# LCmeter0-LCD-8pinlcd-PIC18F2550-COMP.net
KiCad netlist of a schematic drawn in EAGLE
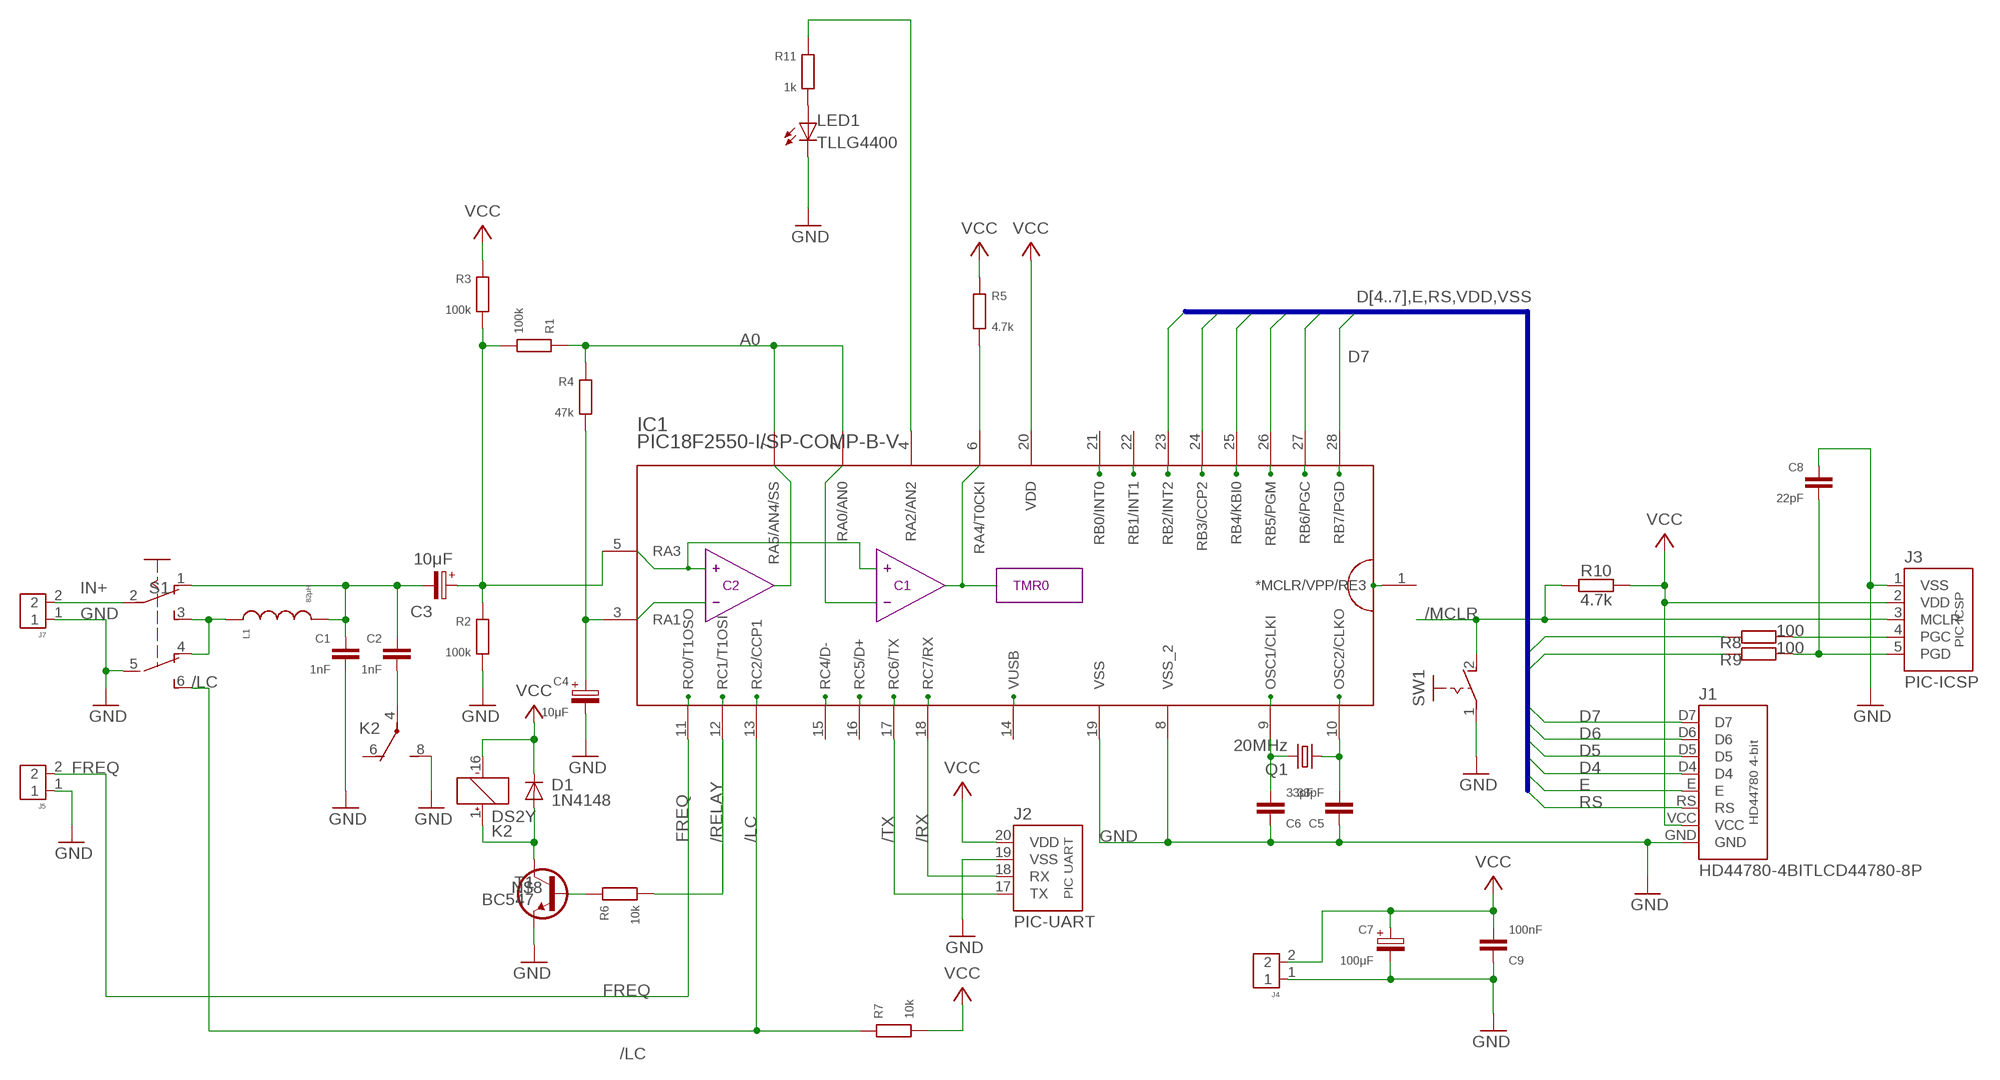
[diagram p0: schematic, sheet 1]

(export (version "E")
  (design (tool "Eeschema 10.0.6"))
  (components
    (comp (ref "C1")
      (value "1nF")
      (footprint "eagle-import:C050-025X060")
      (libsource (lib "eagle-import") (part "C025-025X060"))
    )
    (comp (ref "C2")
      (value "1nF")
      (footprint "eagle-import:C050-025X060")
      (libsource (lib "eagle-import") (part "C025-025X060"))
    )
    (comp (ref "C3")
      (value "10μF")
      (footprint "eagle-import:E2,5-4")
      (libsource (lib "eagle-import") (part "CPOLE2,5-4"))
    )
    (comp (ref "C4")
      (value "10μF")
      (footprint "eagle-import:E2,5-4")
      (libsource (lib "eagle-import") (part "CPOLE2,5-4"))
    )
    (comp (ref "C5")
      (value "33pF")
      (footprint "eagle-import:C025-020X036")
      (libsource (lib "eagle-import") (part "C025-020X036"))
    )
    (comp (ref "C6")
      (value "33pF")
      (footprint "eagle-import:C025-020X036")
      (libsource (lib "eagle-import") (part "C025-020X036"))
    )
    (comp (ref "C7")
      (value "100μF")
      (footprint "eagle-import:E2,5-5")
      (libsource (lib "eagle-import") (part "CPOLE2.5-5"))
    )
    (comp (ref "C8")
      (value "22pF")
      (footprint "eagle-import:C050-020X036")
      (libsource (lib "eagle-import") (part "C050-020X036"))
    )
    (comp (ref "C9")
      (value "100nF")
      (footprint "eagle-import:C025-020X036_V")
      (libsource (lib "eagle-import") (part "C025-020X036/V"))
    )
    (comp (ref "D1")
      (value "1N4148")
      (footprint "eagle-import:DO34-7")
      (libsource (lib "eagle-import") (part "1N414834-7"))
    )
    (comp (ref "IC1")
      (value "PIC18F2550-I/SP-COMP-B-V")
      (footprint "eagle-import:DIL28-3_V")
      (libsource (lib "eagle-import") (part "PIC18F2550-I/SP-COMP-B-V"))
    )
    (comp (ref "J1")
      (value "HD44780-4BITLCD44780-8P")
      (footprint "eagle-import:CONN-LCD44780")
      (libsource (lib "eagle-import") (part "HD44780-4BITLCD44780-8P"))
    )
    (comp (ref "J2")
      (value "PIC-UART")
      (footprint "eagle-import:PIC-UART")
      (libsource (lib "eagle-import") (part "PIC-UART"))
    )
    (comp (ref "J3")
      (value "PIC-ICSP")
      (footprint "eagle-import:PIC-ICSP")
      (libsource (lib "eagle-import") (part "PIC-ICSPICSP"))
    )
    (comp (ref "J4")
      (value "J4")
      (footprint "eagle-import:CONN-2P")
      (libsource (lib "eagle-import") (part "CONN-2P2P/H"))
    )
    (comp (ref "J5")
      (value "CONN-2P2P/V")
      (footprint "eagle-import:CONN-2P-V")
      (libsource (lib "eagle-import") (part "CONN-2P2P/V"))
    )
    (comp (ref "J7")
      (value "CONN-2P2P/V")
      (footprint "eagle-import:CONN-2P-V")
      (libsource (lib "eagle-import") (part "CONN-2P2P/V"))
    )
    (comp (ref "K2")
      (value "DS2Y")
      (footprint "eagle-import:DS2Y")
      (fields (field (name "MPN") "DS2Y-S-DC5V"))
      (libsource (lib "eagle-import") (part "DS2Y-S-DC5V"))
    )
    (comp (ref "L1")
      (value "82μH")
      (footprint "eagle-import:0207_10")
      (libsource (lib "eagle-import") (part "LAXIAL"))
    )
    (comp (ref "LED1")
      (value "TLLG4400")
      (footprint "eagle-import:LED3MM")
      (fields (field (name "MF") "VISHAY SEMICONDUCTOR"))
      (libsource (lib "eagle-import") (part "TLLG4400"))
    )
    (comp (ref "Q1")
      (value "20MHz")
      (footprint "eagle-import:HC49")
      (libsource (lib "eagle-import") (part "CRYSTALHC49"))
    )
    (comp (ref "R1")
      (value "100k")
      (footprint "eagle-import:0202_7")
      (libsource (lib "eagle-import") (part "R0202/7"))
    )
    (comp (ref "R2")
      (value "100k")
      (footprint "eagle-import:0202_7")
      (libsource (lib "eagle-import") (part "R0202/7"))
    )
    (comp (ref "R3")
      (value "100k")
      (footprint "eagle-import:0202_7")
      (libsource (lib "eagle-import") (part "R0202/7"))
    )
    (comp (ref "R4")
      (value "47k")
      (footprint "eagle-import:0202_7")
      (libsource (lib "eagle-import") (part "R0202/7"))
    )
    (comp (ref "R5")
      (value "4.7k")
      (footprint "eagle-import:0202_7")
      (libsource (lib "eagle-import") (part "R0202/7"))
    )
    (comp (ref "R6")
      (value "10k")
      (footprint "eagle-import:0202_7-V")
      (libsource (lib "eagle-import") (part "R0202/7-V"))
    )
    (comp (ref "R7")
      (value "10k")
      (footprint "eagle-import:0202_10-V")
      (libsource (lib "eagle-import") (part "R0202/10-V"))
    )
    (comp (ref "R8")
      (value "100")
      (footprint "eagle-import:0202_7-V")
      (libsource (lib "eagle-import") (part "R0202/7-V"))
    )
    (comp (ref "R9")
      (value "100")
      (footprint "eagle-import:0202_5-V")
      (libsource (lib "eagle-import") (part "R0202/5-V"))
    )
    (comp (ref "R10")
      (value "4.7k")
      (footprint "eagle-import:0202_7")
      (libsource (lib "eagle-import") (part "R0202/7"))
    )
    (comp (ref "R11")
      (value "1k")
      (footprint "eagle-import:0202_5-V")
      (libsource (lib "eagle-import") (part "R0202/5-V"))
    )
    (comp (ref "S1")
      (value "SL-SW-2P-2T")
      (footprint "eagle-import:SLSW-2P2T")
      (libsource (lib "eagle-import") (part "SL-SW-2P-2T"))
    )
    (comp (ref "SW1")
      (value "PB-1P-1T")
      (footprint "eagle-import:PB-1P1T")
      (libsource (lib "eagle-import") (part "PB-1P-1T"))
    )
    (comp (ref "T1")
      (value "BC547")
      (footprint "eagle-import:TO92-CBE-A")
      (libsource (lib "eagle-import") (part "BC547CBE-A"))
    )
  )
  (nets
    (net (code "3") (name "/A0") (class "Default")
      (node (ref "IC1") (pin "2") (pinfunction "RA0/AN0_2") (pintype "passive"))
      (node (ref "IC1") (pin "7") (pinfunction "RA5/AN4/SS_7") (pintype "passive"))
      (node (ref "R1") (pin "2") (pinfunction "2_2") (pintype "passive"))
      (node (ref "R4") (pin "2") (pinfunction "2_2") (pintype "passive"))
    )
    (net (code "4") (name "/D4") (class "Default")
      (node (ref "IC1") (pin "25") (pinfunction "RB4/KBI0_25") (pintype "passive"))
      (node (ref "J1") (pin "D4") (pinfunction "D4_D4") (pintype "passive"))
    )
    (net (code "5") (name "/D5") (class "Default")
      (node (ref "IC1") (pin "26") (pinfunction "RB5/PGM_26") (pintype "passive"))
      (node (ref "J1") (pin "D5") (pinfunction "D5_D5") (pintype "passive"))
    )
    (net (code "6") (name "/D6") (class "Default")
      (node (ref "IC1") (pin "27") (pinfunction "RB6/PGC_27") (pintype "passive"))
      (node (ref "J1") (pin "D6") (pinfunction "D6_D6") (pintype "passive"))
      (node (ref "R8") (pin "2") (pinfunction "2_2") (pintype "passive"))
    )
    (net (code "7") (name "/D7") (class "Default")
      (node (ref "IC1") (pin "28") (pinfunction "RB7/PGD_28") (pintype "passive"))
      (node (ref "J1") (pin "D7") (pinfunction "D7_D7") (pintype "passive"))
      (node (ref "R9") (pin "2") (pinfunction "2_2") (pintype "passive"))
    )
    (net (code "8") (name "/E") (class "Default")
      (node (ref "IC1") (pin "24") (pinfunction "RB3/CCP2_24") (pintype "passive"))
      (node (ref "J1") (pin "E") (pinfunction "E_E") (pintype "passive"))
    )
    (net (code "9") (name "/FREQ") (class "Default")
      (node (ref "IC1") (pin "11") (pinfunction "RC0/T1OSO_11") (pintype "passive"))
      (node (ref "J5") (pin "2") (pinfunction "2_2") (pintype "bidirectional"))
    )
    (net (code "10") (name "/IN+") (class "Default")
      (node (ref "J7") (pin "2") (pinfunction "2_2") (pintype "bidirectional"))
      (node (ref "S1") (pin "2") (pinfunction "P_2") (pintype "passive"))
    )
    (net (code "11") (name "/N$8") (class "Default")
      (node (ref "D1") (pin "A") (pinfunction "A_A") (pintype "passive"))
      (node (ref "K2") (pin "1") (pinfunction "+_1") (pintype "passive"))
      (node (ref "T1") (pin "C") (pinfunction "C_C") (pintype "passive"))
    )
    (net (code "12") (name "/RS") (class "Default")
      (node (ref "IC1") (pin "23") (pinfunction "RB2/INT2_23") (pintype "passive"))
      (node (ref "J1") (pin "RS") (pinfunction "RS_RS") (pintype "passive"))
    )
    (net (code "14") (name "/{slash}LC") (class "Default")
      (node (ref "IC1") (pin "13") (pinfunction "RC2/CCP1_13") (pintype "passive"))
      (node (ref "R7") (pin "2") (pinfunction "2_2") (pintype "passive"))
      (node (ref "S1") (pin "6") (pinfunction "S1_6") (pintype "passive"))
    )
    (net (code "15") (name "/{slash}MCLR") (class "Default")
      (node (ref "J3") (pin "3") (pinfunction "MCLR_3") (pintype "passive"))
      (node (ref "R10") (pin "2") (pinfunction "2_2") (pintype "passive"))
      (node (ref "SW1") (pin "2") (pinfunction "S_2") (pintype "passive"))
    )
    (net (code "16") (name "/{slash}RELAY") (class "Default")
      (node (ref "IC1") (pin "12") (pinfunction "RC1/T1OSI_12") (pintype "passive"))
      (node (ref "R6") (pin "1") (pinfunction "1_1") (pintype "passive"))
    )
    (net (code "17") (name "/{slash}RX") (class "Default")
      (node (ref "IC1") (pin "18") (pinfunction "RC7/RX_18") (pintype "passive"))
      (node (ref "J2") (pin "18") (pinfunction "RX_18") (pintype "passive"))
    )
    (net (code "18") (name "/{slash}TX") (class "Default")
      (node (ref "IC1") (pin "17") (pinfunction "RC6/TX_17") (pintype "passive"))
      (node (ref "J2") (pin "17") (pinfunction "TX_17") (pintype "passive"))
    )
    (net (code "19") (name "GND") (class "Default")
      (node (ref "C1") (pin "2") (pinfunction "2_2") (pintype "passive"))
      (node (ref "C4") (pin "-") (pinfunction "-_-") (pintype "passive"))
      (node (ref "C5") (pin "1") (pinfunction "1_1") (pintype "passive"))
      (node (ref "C6") (pin "1") (pinfunction "1_1") (pintype "passive"))
      (node (ref "C7") (pin "-") (pinfunction "-_-") (pintype "passive"))
      (node (ref "C8") (pin "1") (pinfunction "1_1") (pintype "passive"))
      (node (ref "C9") (pin "1") (pinfunction "1_1") (pintype "passive"))
      (node (ref "IC1") (pin "19") (pinfunction "VSS_19") (pintype "passive"))
      (node (ref "IC1") (pin "8") (pinfunction "VSS_2_8") (pintype "passive"))
      (node (ref "J1") (pin "GND") (pinfunction "GND_GND") (pintype "passive"))
      (node (ref "J2") (pin "19") (pinfunction "VSS_19") (pintype "passive"))
      (node (ref "J3") (pin "1") (pinfunction "VSS_1") (pintype "passive"))
      (node (ref "J4") (pin "1") (pinfunction "1_1") (pintype "bidirectional"))
      (node (ref "J5") (pin "1") (pinfunction "1_1") (pintype "bidirectional"))
      (node (ref "J7") (pin "1") (pinfunction "1_1") (pintype "bidirectional"))
      (node (ref "K2") (pin "8") (pinfunction "S_8") (pintype "passive"))
      (node (ref "LED1") (pin "K") (pinfunction "C_K") (pintype "passive"))
      (node (ref "R2") (pin "1") (pinfunction "1_1") (pintype "passive"))
      (node (ref "S1") (pin "5") (pinfunction "P1_5") (pintype "passive"))
      (node (ref "SW1") (pin "1") (pinfunction "P_1") (pintype "passive"))
      (node (ref "T1") (pin "E") (pinfunction "E_E") (pintype "passive"))
    )
    (net (code "20") (name "Net-(IC1-OSC1{slash}CLKI)") (class "Default")
      (node (ref "C6") (pin "2") (pinfunction "2_2") (pintype "passive"))
      (node (ref "IC1") (pin "9") (pinfunction "OSC1/CLKI_9") (pintype "passive"))
      (node (ref "Q1") (pin "2") (pinfunction "2_2") (pintype "passive"))
    )
    (net (code "21") (name "Net-(IC1-OSC2{slash}CLKO)") (class "Default")
      (node (ref "C5") (pin "2") (pinfunction "2_2") (pintype "passive"))
      (node (ref "IC1") (pin "10") (pinfunction "OSC2/CLKO_10") (pintype "passive"))
      (node (ref "Q1") (pin "1") (pinfunction "1_1") (pintype "passive"))
    )
    (net (code "22") (name "Net-(IC1-RA1)") (class "Default")
      (node (ref "C4") (pin "+") (pinfunction "+_+") (pintype "passive"))
      (node (ref "IC1") (pin "3") (pinfunction "RA1_3") (pintype "passive"))
      (node (ref "R4") (pin "1") (pinfunction "1_1") (pintype "passive"))
    )
    (net (code "23") (name "Net-(IC1-RA2{slash}AN2)") (class "Default")
      (node (ref "IC1") (pin "4") (pinfunction "RA2/AN2_4") (pintype "passive"))
      (node (ref "R11") (pin "2") (pinfunction "2_2") (pintype "passive"))
    )
    (net (code "24") (name "Net-(IC1-RA3)") (class "Default")
      (node (ref "C3") (pin "+") (pinfunction "+_+") (pintype "passive"))
      (node (ref "IC1") (pin "5") (pinfunction "RA3_5") (pintype "passive"))
      (node (ref "R1") (pin "1") (pinfunction "1_1") (pintype "passive"))
      (node (ref "R2") (pin "2") (pinfunction "2_2") (pintype "passive"))
      (node (ref "R3") (pin "1") (pinfunction "1_1") (pintype "passive"))
    )
    (net (code "25") (name "Net-(IC1-RA4{slash}T0CKI)") (class "Default")
      (node (ref "IC1") (pin "6") (pinfunction "RA4/T0CKI_6") (pintype "passive"))
      (node (ref "R5") (pin "1") (pinfunction "1_1") (pintype "passive"))
    )
    (net (code "26") (name "Net-(J3-PGC)") (class "Default")
      (node (ref "J3") (pin "4") (pinfunction "PGC_4") (pintype "passive"))
      (node (ref "R8") (pin "1") (pinfunction "1_1") (pintype "passive"))
    )
    (net (code "27") (name "Net-(J3-PGD)") (class "Default")
      (node (ref "C8") (pin "2") (pinfunction "2_2") (pintype "passive"))
      (node (ref "J3") (pin "5") (pinfunction "PGD_5") (pintype "passive"))
      (node (ref "R9") (pin "1") (pinfunction "1_1") (pintype "passive"))
    )
    (net (code "28") (name "Net-(K2B-P)") (class "Default")
      (node (ref "C2") (pin "2") (pinfunction "2_2") (pintype "passive"))
      (node (ref "K2") (pin "4") (pinfunction "P_4") (pintype "passive"))
    )
    (net (code "29") (name "Net-(LED1-PadA)") (class "Default")
      (node (ref "LED1") (pin "A") (pinfunction "A_A") (pintype "passive"))
      (node (ref "R11") (pin "1") (pinfunction "1_1") (pintype "passive"))
    )
    (net (code "30") (name "Net-(R6-Pad2)") (class "Default")
      (node (ref "R6") (pin "2") (pinfunction "2_2") (pintype "passive"))
      (node (ref "T1") (pin "B") (pinfunction "B_B") (pintype "passive"))
    )
    (net (code "31") (name "Net-(S1-O)") (class "Default")
      (node (ref "C1") (pin "1") (pinfunction "1_1") (pintype "passive"))
      (node (ref "C2") (pin "1") (pinfunction "1_1") (pintype "passive"))
      (node (ref "C3") (pin "-") (pinfunction "-_-") (pintype "passive"))
      (node (ref "L1") (pin "2") (pinfunction "2_2") (pintype "passive"))
      (node (ref "S1") (pin "1") (pinfunction "O_1") (pintype "passive"))
    )
    (net (code "32") (name "Net-(S1-O1)") (class "Default")
      (node (ref "L1") (pin "1") (pinfunction "1_1") (pintype "passive"))
      (node (ref "S1") (pin "3") (pinfunction "S_3") (pintype "passive"))
      (node (ref "S1") (pin "4") (pinfunction "O1_4") (pintype "passive"))
    )
    (net (code "33") (name "VCC") (class "Default")
      (node (ref "C7") (pin "+") (pinfunction "+_+") (pintype "passive"))
      (node (ref "C9") (pin "2") (pinfunction "2_2") (pintype "passive"))
      (node (ref "D1") (pin "C") (pinfunction "C_C") (pintype "passive"))
      (node (ref "IC1") (pin "20") (pinfunction "VDD_20") (pintype "passive"))
      (node (ref "J1") (pin "VCC") (pinfunction "VCC_VCC") (pintype "passive"))
      (node (ref "J2") (pin "20") (pinfunction "VDD_20") (pintype "passive"))
      (node (ref "J3") (pin "2") (pinfunction "VDD_2") (pintype "passive"))
      (node (ref "J4") (pin "2") (pinfunction "2_2") (pintype "bidirectional"))
      (node (ref "K2") (pin "16") (pinfunction "-_16") (pintype "passive"))
      (node (ref "R10") (pin "1") (pinfunction "1_1") (pintype "passive"))
      (node (ref "R3") (pin "2") (pinfunction "2_2") (pintype "passive"))
      (node (ref "R5") (pin "2") (pinfunction "2_2") (pintype "passive"))
      (node (ref "R7") (pin "1") (pinfunction "1_1") (pintype "passive"))
    )
    (net (code "34") (name "unconnected-(IC1-*MCLR{slash}VPP{slash}RE3-Pad1)") (class "Default")
      (node (ref "IC1") (pin "1") (pinfunction "*MCLR/VPP/RE3_1") (pintype "passive"))
    )
    (net (code "35") (name "unconnected-(IC1-RB0{slash}INT0-Pad21)") (class "Default")
      (node (ref "IC1") (pin "21") (pinfunction "RB0/INT0_21") (pintype "passive"))
    )
    (net (code "36") (name "unconnected-(IC1-RB1{slash}INT1-Pad22)") (class "Default")
      (node (ref "IC1") (pin "22") (pinfunction "RB1/INT1_22") (pintype "passive"))
    )
    (net (code "37") (name "unconnected-(IC1-RC4{slash}D--Pad15)") (class "Default")
      (node (ref "IC1") (pin "15") (pinfunction "RC4/D-_15") (pintype "passive"))
    )
    (net (code "38") (name "unconnected-(IC1-RC5{slash}D+-Pad16)") (class "Default")
      (node (ref "IC1") (pin "16") (pinfunction "RC5/D+_16") (pintype "passive"))
    )
    (net (code "39") (name "unconnected-(IC1-VUSB-Pad14)") (class "Default")
      (node (ref "IC1") (pin "14") (pinfunction "VUSB_14") (pintype "passive"))
    )
    (net (code "40") (name "unconnected-(K2B-O-Pad6)") (class "Default")
      (node (ref "K2") (pin "6") (pinfunction "O_6") (pintype "passive"))
    )
  )
)
